# 2_mb_conn.net
KiCad netlist of a schematic drawn in Altium Designer
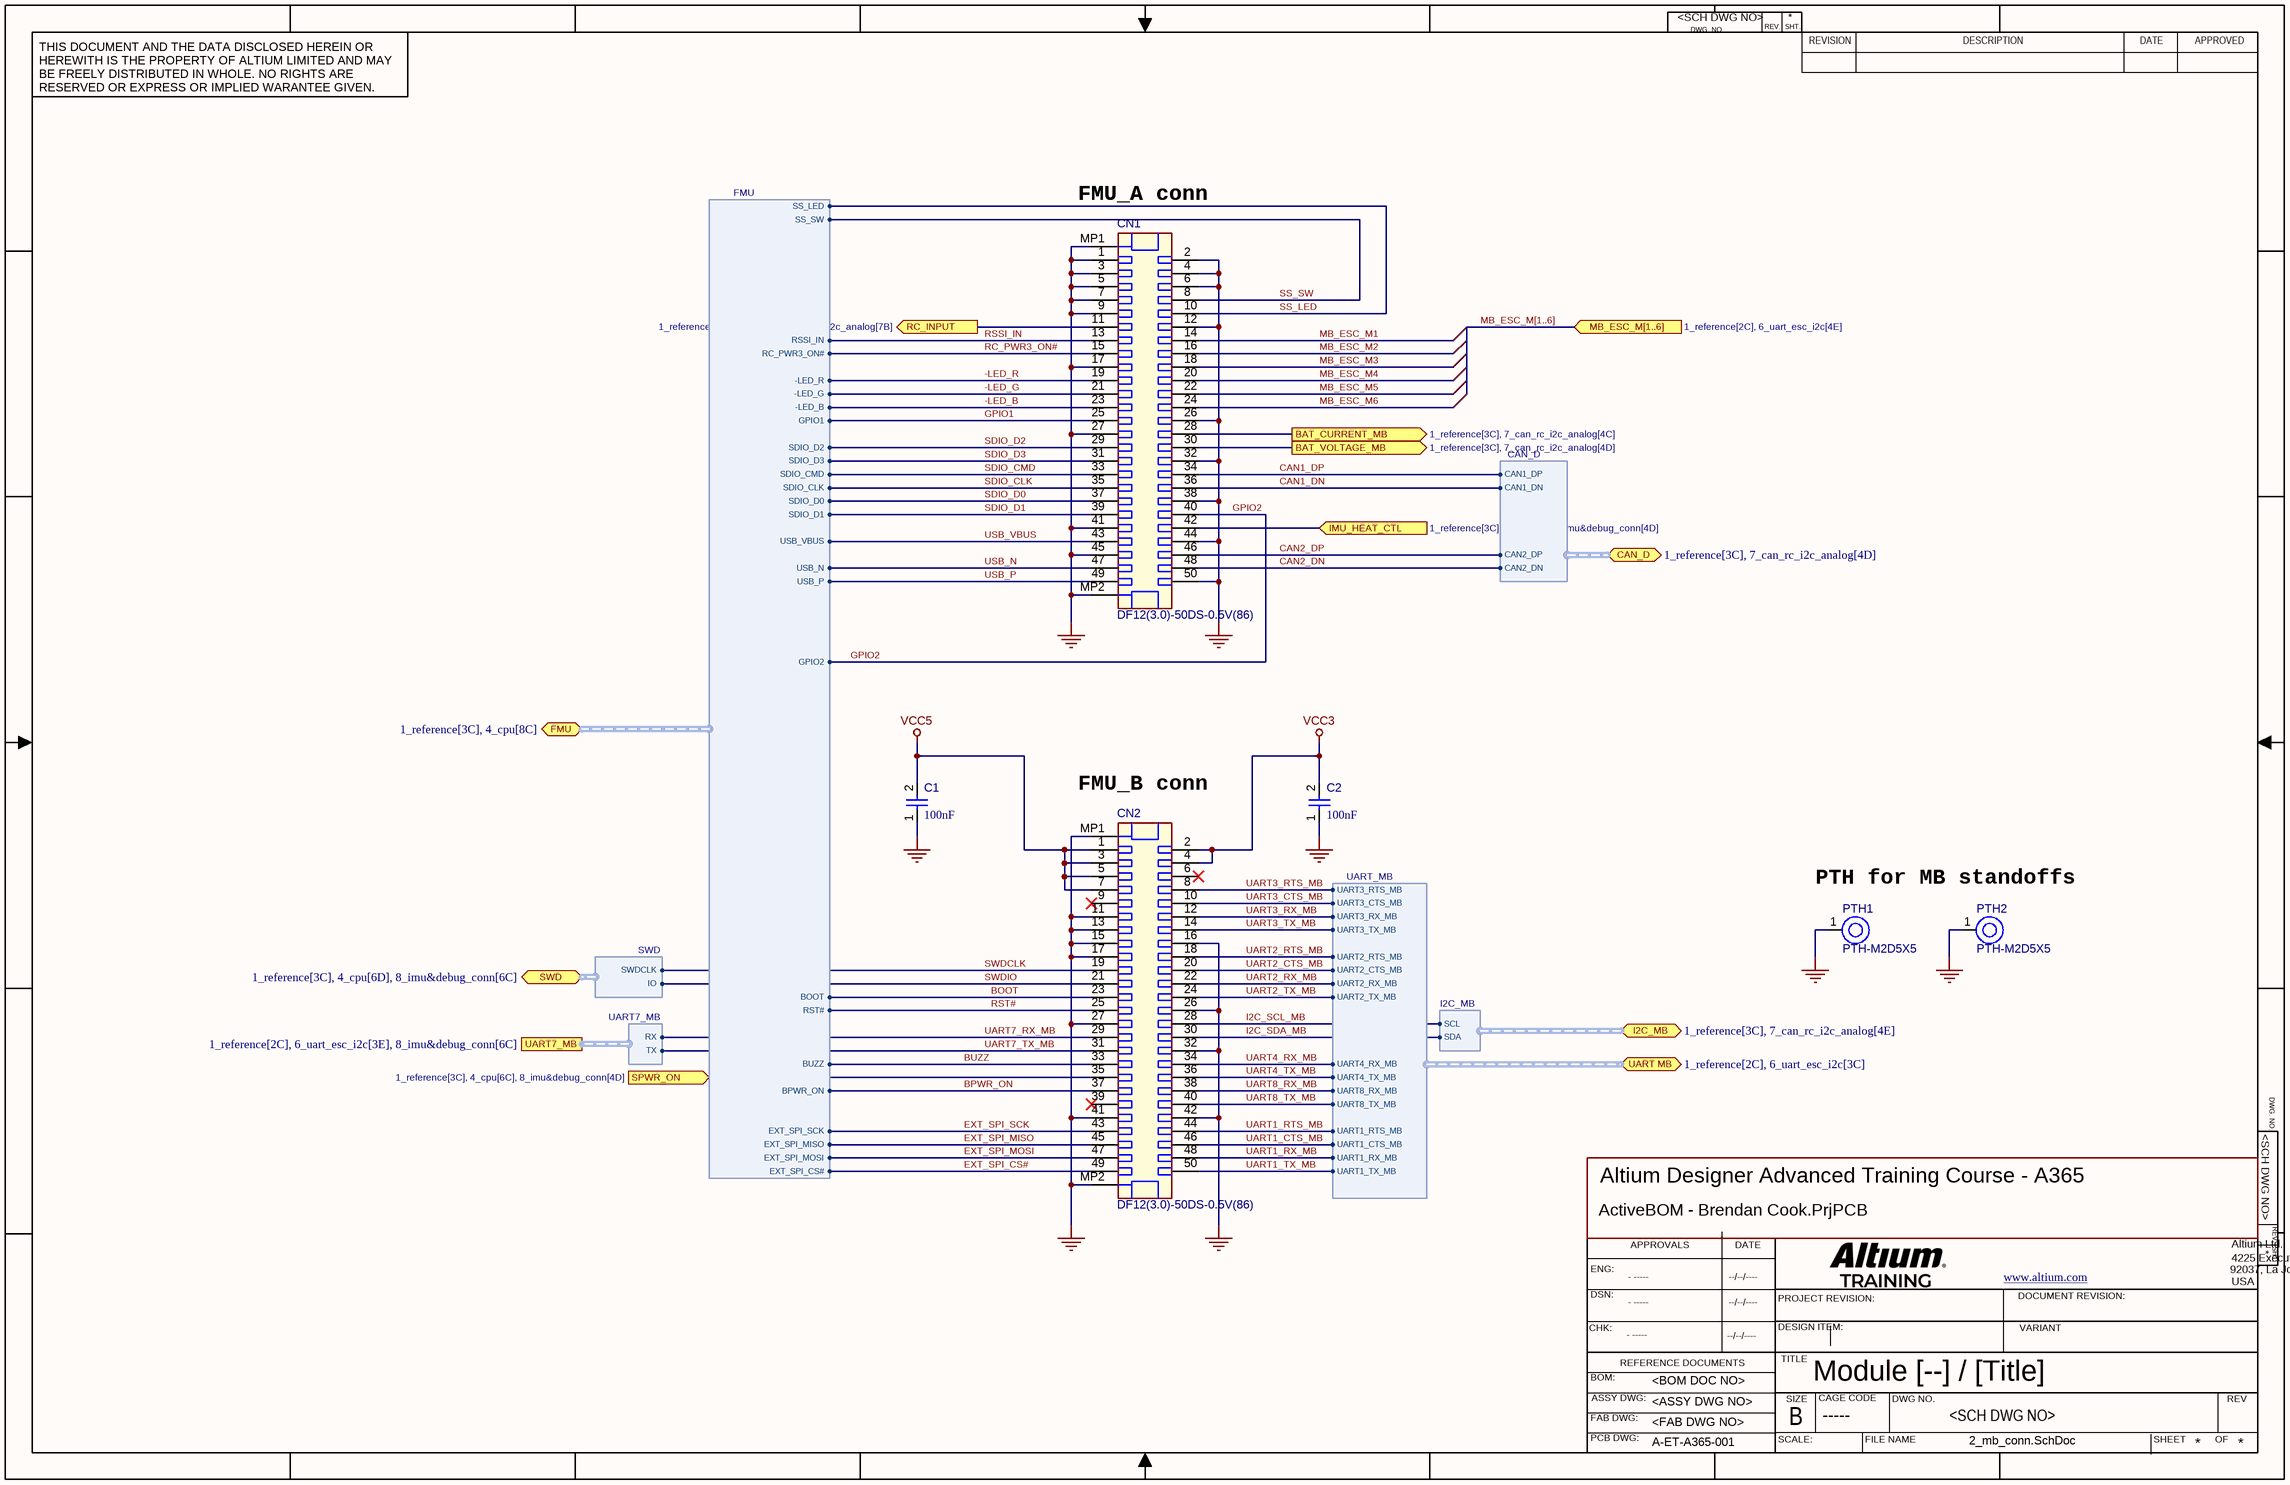
[diagram p0: 2_mb_conn.SchDoc]

(export (version "E")
  (design (tool "Eeschema 10.0.6"))
  (components
    (comp (ref "C1")
      (value "100nF")
      (footprint "CAPC0402(1005)60_L")
      (description "Chip Capacitor, 100nF +/-20%, 10V, 0402, Thickness 0.6 mm")
      (fields (field (name "TOLERANCE") "20%") (field (name "Comment") "Capacitor 100nF +/-20% 10V 0402"))
      (libsource (lib "MHH -  Altium Advanced Course A365 01") (part "CAP-NP-2"))
    )
    (comp (ref "C2")
      (value "100nF")
      (footprint "CAPC0402(1005)60_L")
      (description "Chip Capacitor, 100nF +/-20%, 10V, 0402, Thickness 0.6 mm")
      (fields (field (name "TOLERANCE") "20%") (field (name "Comment") "Capacitor 100nF +/-20% 10V 0402"))
      (libsource (lib "MHH -  Altium Advanced Course A365 01") (part "CAP-NP-2"))
    )
    (comp (ref "CN1")
      (value "DF12(3.0)-50DS-0.5V(86)")
      (footprint "HIRO-DF12(3.0)-50DS-0.5V_V")
      (description "Receptacle Connector, 50 V, 0.3 A, -45 to 125 degC, RoHS, Tape and Reel")
      (libsource (lib "MHH -  Altium Advanced Course A365 01") (part "CMP-00111-4"))
    )
    (comp (ref "CN2")
      (value "DF12(3.0)-50DS-0.5V(86)")
      (footprint "HIRO-DF12(3.0)-50DS-0.5V_V")
      (description "Receptacle Connector, 50 V, 0.3 A, -45 to 125 degC, RoHS, Tape and Reel")
      (libsource (lib "MHH -  Altium Advanced Course A365 01") (part "CMP-00111-4"))
    )
    (comp (ref "PTH1")
      (value "PTH-M2D5X5")
      (footprint "PTH-M2D5X5")
      (description "M2 PTH (2.5mm), 5mm pad")
      (libsource (lib "MHH -  Altium Advanced Course A365 01") (part "CMP-00028-00000-1"))
    )
    (comp (ref "PTH2")
      (value "PTH-M2D5X5")
      (footprint "PTH-M2D5X5")
      (description "M2 PTH (2.5mm), 5mm pad")
      (libsource (lib "MHH -  Altium Advanced Course A365 01") (part "CMP-00028-00000-1"))
    )
  )
  (nets
    (net (code "7") (name "/-LED_B") (class "Default")
      (node (ref "CN1") (pin "23") (pinfunction "23_23") (pintype "passive"))
    )
    (net (code "8") (name "/-LED_G") (class "Default")
      (node (ref "CN1") (pin "21") (pinfunction "21_21") (pintype "passive"))
    )
    (net (code "9") (name "/-LED_R") (class "Default")
      (node (ref "CN1") (pin "19") (pinfunction "19_19") (pintype "passive"))
    )
    (net (code "10") (name "/BAT_CURRENT_MB") (class "Default")
      (node (ref "CN1") (pin "28") (pinfunction "28_28") (pintype "passive"))
    )
    (net (code "11") (name "/BAT_VOLTAGE_MB") (class "Default")
      (node (ref "CN1") (pin "30") (pinfunction "30_30") (pintype "passive"))
    )
    (net (code "12") (name "/BOOT") (class "Default")
      (node (ref "CN2") (pin "23") (pinfunction "23_23") (pintype "passive"))
    )
    (net (code "13") (name "/BPWR_ON") (class "Default")
      (node (ref "CN2") (pin "37") (pinfunction "37_37") (pintype "passive"))
    )
    (net (code "14") (name "/BUZZ") (class "Default")
      (node (ref "CN2") (pin "33") (pinfunction "33_33") (pintype "passive"))
    )
    (net (code "15") (name "/CAN1_DN") (class "Default")
      (node (ref "CN1") (pin "36") (pinfunction "36_36") (pintype "passive"))
    )
    (net (code "16") (name "/CAN1_DP") (class "Default")
      (node (ref "CN1") (pin "34") (pinfunction "34_34") (pintype "passive"))
    )
    (net (code "17") (name "/CAN2_DN") (class "Default")
      (node (ref "CN1") (pin "48") (pinfunction "48_48") (pintype "passive"))
    )
    (net (code "18") (name "/CAN2_DP") (class "Default")
      (node (ref "CN1") (pin "46") (pinfunction "46_46") (pintype "passive"))
    )
    (net (code "19") (name "/EXT_SPI_CS#") (class "Default")
      (node (ref "CN2") (pin "49") (pinfunction "49_49") (pintype "passive"))
    )
    (net (code "20") (name "/EXT_SPI_MISO") (class "Default")
      (node (ref "CN2") (pin "45") (pinfunction "45_45") (pintype "passive"))
    )
    (net (code "21") (name "/EXT_SPI_MOSI") (class "Default")
      (node (ref "CN2") (pin "47") (pinfunction "47_47") (pintype "passive"))
    )
    (net (code "22") (name "/EXT_SPI_SCK") (class "Default")
      (node (ref "CN2") (pin "43") (pinfunction "43_43") (pintype "passive"))
    )
    (net (code "23") (name "/GPIO1") (class "Default")
      (node (ref "CN1") (pin "25") (pinfunction "25_25") (pintype "passive"))
    )
    (net (code "24") (name "/GPIO2") (class "Default")
      (node (ref "CN1") (pin "40") (pinfunction "40_40") (pintype "passive"))
    )
    (net (code "25") (name "/I2C_SCL_MB") (class "Default")
      (node (ref "CN2") (pin "28") (pinfunction "28_28") (pintype "passive"))
    )
    (net (code "26") (name "/I2C_SDA_MB") (class "Default")
      (node (ref "CN2") (pin "30") (pinfunction "30_30") (pintype "passive"))
    )
    (net (code "27") (name "/IMU_HEAT_CTL") (class "Default")
      (node (ref "CN1") (pin "42") (pinfunction "42_42") (pintype "passive"))
    )
    (net (code "28") (name "/MB_ESC_M1") (class "Default")
      (node (ref "CN1") (pin "14") (pinfunction "14_14") (pintype "passive"))
    )
    (net (code "29") (name "/MB_ESC_M2") (class "Default")
      (node (ref "CN1") (pin "16") (pinfunction "16_16") (pintype "passive"))
    )
    (net (code "30") (name "/MB_ESC_M3") (class "Default")
      (node (ref "CN1") (pin "18") (pinfunction "18_18") (pintype "passive"))
    )
    (net (code "31") (name "/MB_ESC_M4") (class "Default")
      (node (ref "CN1") (pin "20") (pinfunction "20_20") (pintype "passive"))
    )
    (net (code "32") (name "/MB_ESC_M5") (class "Default")
      (node (ref "CN1") (pin "22") (pinfunction "22_22") (pintype "passive"))
    )
    (net (code "33") (name "/MB_ESC_M6") (class "Default")
      (node (ref "CN1") (pin "24") (pinfunction "24_24") (pintype "passive"))
    )
    (net (code "35") (name "/RC_INPUT") (class "Default")
      (node (ref "CN1") (pin "11") (pinfunction "11_11") (pintype "passive"))
    )
    (net (code "36") (name "/RC_PWR3_ON#") (class "Default")
      (node (ref "CN1") (pin "15") (pinfunction "15_15") (pintype "passive"))
    )
    (net (code "37") (name "/RSSI_IN") (class "Default")
      (node (ref "CN1") (pin "13") (pinfunction "13_13") (pintype "passive"))
    )
    (net (code "38") (name "/RST#") (class "Default")
      (node (ref "CN2") (pin "25") (pinfunction "25_25") (pintype "passive"))
    )
    (net (code "39") (name "/SDIO_CLK") (class "Default")
      (node (ref "CN1") (pin "35") (pinfunction "35_35") (pintype "passive"))
    )
    (net (code "40") (name "/SDIO_CMD") (class "Default")
      (node (ref "CN1") (pin "33") (pinfunction "33_33") (pintype "passive"))
    )
    (net (code "41") (name "/SDIO_D0") (class "Default")
      (node (ref "CN1") (pin "37") (pinfunction "37_37") (pintype "passive"))
    )
    (net (code "42") (name "/SDIO_D1") (class "Default")
      (node (ref "CN1") (pin "39") (pinfunction "39_39") (pintype "passive"))
    )
    (net (code "43") (name "/SDIO_D2") (class "Default")
      (node (ref "CN1") (pin "29") (pinfunction "29_29") (pintype "passive"))
    )
    (net (code "44") (name "/SDIO_D3") (class "Default")
      (node (ref "CN1") (pin "31") (pinfunction "31_31") (pintype "passive"))
    )
    (net (code "45") (name "/SPWR_ON") (class "Default")
      (node (ref "CN2") (pin "35") (pinfunction "35_35") (pintype "passive"))
    )
    (net (code "46") (name "/SS_LED") (class "Default")
      (node (ref "CN1") (pin "10") (pinfunction "10_10") (pintype "passive"))
    )
    (net (code "47") (name "/SS_SW") (class "Default")
      (node (ref "CN1") (pin "8") (pinfunction "8_8") (pintype "passive"))
    )
    (net (code "48") (name "/SWDCLK") (class "Default")
      (node (ref "CN2") (pin "19") (pinfunction "19_19") (pintype "passive"))
    )
    (net (code "49") (name "/SWDIO") (class "Default")
      (node (ref "CN2") (pin "21") (pinfunction "21_21") (pintype "passive"))
    )
    (net (code "50") (name "/UART1_CTS_MB") (class "Default")
      (node (ref "CN2") (pin "46") (pinfunction "46_46") (pintype "passive"))
    )
    (net (code "51") (name "/UART1_RTS_MB") (class "Default")
      (node (ref "CN2") (pin "44") (pinfunction "44_44") (pintype "passive"))
    )
    (net (code "52") (name "/UART1_RX_MB") (class "Default")
      (node (ref "CN2") (pin "48") (pinfunction "48_48") (pintype "passive"))
    )
    (net (code "53") (name "/UART1_TX_MB") (class "Default")
      (node (ref "CN2") (pin "50") (pinfunction "50_50") (pintype "passive"))
    )
    (net (code "54") (name "/UART2_CTS_MB") (class "Default")
      (node (ref "CN2") (pin "20") (pinfunction "20_20") (pintype "passive"))
    )
    (net (code "55") (name "/UART2_RTS_MB") (class "Default")
      (node (ref "CN2") (pin "18") (pinfunction "18_18") (pintype "passive"))
    )
    (net (code "56") (name "/UART2_RX_MB") (class "Default")
      (node (ref "CN2") (pin "22") (pinfunction "22_22") (pintype "passive"))
    )
    (net (code "57") (name "/UART2_TX_MB") (class "Default")
      (node (ref "CN2") (pin "24") (pinfunction "24_24") (pintype "passive"))
    )
    (net (code "58") (name "/UART3_CTS_MB") (class "Default")
      (node (ref "CN2") (pin "10") (pinfunction "10_10") (pintype "passive"))
    )
    (net (code "59") (name "/UART3_RTS_MB") (class "Default")
      (node (ref "CN2") (pin "8") (pinfunction "8_8") (pintype "passive"))
    )
    (net (code "60") (name "/UART3_RX_MB") (class "Default")
      (node (ref "CN2") (pin "12") (pinfunction "12_12") (pintype "passive"))
    )
    (net (code "61") (name "/UART3_TX_MB") (class "Default")
      (node (ref "CN2") (pin "14") (pinfunction "14_14") (pintype "passive"))
    )
    (net (code "62") (name "/UART4_RX_MB") (class "Default")
      (node (ref "CN2") (pin "34") (pinfunction "34_34") (pintype "passive"))
    )
    (net (code "63") (name "/UART4_TX_MB") (class "Default")
      (node (ref "CN2") (pin "36") (pinfunction "36_36") (pintype "passive"))
    )
    (net (code "64") (name "/UART7_RX_MB") (class "Default")
      (node (ref "CN2") (pin "29") (pinfunction "29_29") (pintype "passive"))
    )
    (net (code "65") (name "/UART7_TX_MB") (class "Default")
      (node (ref "CN2") (pin "31") (pinfunction "31_31") (pintype "passive"))
    )
    (net (code "66") (name "/UART8_RX_MB") (class "Default")
      (node (ref "CN2") (pin "38") (pinfunction "38_38") (pintype "passive"))
    )
    (net (code "67") (name "/UART8_TX_MB") (class "Default")
      (node (ref "CN2") (pin "40") (pinfunction "40_40") (pintype "passive"))
    )
    (net (code "68") (name "/USB_N") (class "Default")
      (node (ref "CN1") (pin "47") (pinfunction "47_47") (pintype "passive"))
    )
    (net (code "69") (name "/USB_P") (class "Default")
      (node (ref "CN1") (pin "49") (pinfunction "49_49") (pintype "passive"))
    )
    (net (code "70") (name "/USB_VBUS") (class "Default")
      (node (ref "CN1") (pin "43") (pinfunction "43_43") (pintype "passive"))
    )
    (net (code "77") (name "GND") (class "Default")
      (node (ref "C1") (pin "1") (pinfunction "1_1") (pintype "passive"))
      (node (ref "C2") (pin "1") (pinfunction "1_1") (pintype "passive"))
      (node (ref "CN1") (pin "1") (pinfunction "1_1") (pintype "passive"))
      (node (ref "CN1") (pin "12") (pinfunction "12_12") (pintype "passive"))
      (node (ref "CN1") (pin "17") (pinfunction "17_17") (pintype "passive"))
      (node (ref "CN1") (pin "2") (pinfunction "2_2") (pintype "passive"))
      (node (ref "CN1") (pin "26") (pinfunction "26_26") (pintype "passive"))
      (node (ref "CN1") (pin "27") (pinfunction "27_27") (pintype "passive"))
      (node (ref "CN1") (pin "3") (pinfunction "3_3") (pintype "passive"))
      (node (ref "CN1") (pin "32") (pinfunction "32_32") (pintype "passive"))
      (node (ref "CN1") (pin "38") (pinfunction "38_38") (pintype "passive"))
      (node (ref "CN1") (pin "4") (pinfunction "4_4") (pintype "passive"))
      (node (ref "CN1") (pin "41") (pinfunction "41_41") (pintype "passive"))
      (node (ref "CN1") (pin "44") (pinfunction "44_44") (pintype "passive"))
      (node (ref "CN1") (pin "45") (pinfunction "45_45") (pintype "passive"))
      (node (ref "CN1") (pin "5") (pinfunction "5_5") (pintype "passive"))
      (node (ref "CN1") (pin "50") (pinfunction "50_50") (pintype "passive"))
      (node (ref "CN1") (pin "6") (pinfunction "6_6") (pintype "passive"))
      (node (ref "CN1") (pin "7") (pinfunction "7_7") (pintype "passive"))
      (node (ref "CN1") (pin "9") (pinfunction "9_9") (pintype "passive"))
      (node (ref "CN1") (pin "MP1") (pinfunction "MP1_MP1") (pintype "passive"))
      (node (ref "CN1") (pin "MP2") (pinfunction "MP2_MP2") (pintype "passive"))
      (node (ref "CN2") (pin "11") (pinfunction "11_11") (pintype "passive"))
      (node (ref "CN2") (pin "13") (pinfunction "13_13") (pintype "passive"))
      (node (ref "CN2") (pin "15") (pinfunction "15_15") (pintype "passive"))
      (node (ref "CN2") (pin "16") (pinfunction "16_16") (pintype "passive"))
      (node (ref "CN2") (pin "17") (pinfunction "17_17") (pintype "passive"))
      (node (ref "CN2") (pin "26") (pinfunction "26_26") (pintype "passive"))
      (node (ref "CN2") (pin "27") (pinfunction "27_27") (pintype "passive"))
      (node (ref "CN2") (pin "32") (pinfunction "32_32") (pintype "passive"))
      (node (ref "CN2") (pin "41") (pinfunction "41_41") (pintype "passive"))
      (node (ref "CN2") (pin "42") (pinfunction "42_42") (pintype "passive"))
      (node (ref "CN2") (pin "MP1") (pinfunction "MP1_MP1") (pintype "passive"))
      (node (ref "CN2") (pin "MP2") (pinfunction "MP2_MP2") (pintype "passive"))
      (node (ref "PTH1") (pin "1") (pinfunction "H1_1") (pintype "passive"))
      (node (ref "PTH2") (pin "1") (pinfunction "H1_1") (pintype "passive"))
    )
    (net (code "78") (name "VCC3") (class "Default")
      (node (ref "C2") (pin "2") (pinfunction "2_2") (pintype "passive"))
      (node (ref "CN2") (pin "2") (pinfunction "2_2") (pintype "passive"))
      (node (ref "CN2") (pin "4") (pinfunction "4_4") (pintype "passive"))
    )
    (net (code "79") (name "VCC5") (class "Default")
      (node (ref "C1") (pin "2") (pinfunction "2_2") (pintype "passive"))
      (node (ref "CN2") (pin "1") (pinfunction "1_1") (pintype "passive"))
      (node (ref "CN2") (pin "3") (pinfunction "3_3") (pintype "passive"))
      (node (ref "CN2") (pin "5") (pinfunction "5_5") (pintype "passive"))
      (node (ref "CN2") (pin "7") (pinfunction "7_7") (pintype "passive"))
    )
    (net (code "80") (name "unconnected-(CN2-Pad6)") (class "Default")
      (node (ref "CN2") (pin "6") (pinfunction "6_6") (pintype "passive+no_connect"))
    )
    (net (code "81") (name "unconnected-(CN2-Pad9)") (class "Default")
      (node (ref "CN2") (pin "9") (pinfunction "9_9") (pintype "passive+no_connect"))
    )
    (net (code "82") (name "unconnected-(CN2-Pad39)") (class "Default")
      (node (ref "CN2") (pin "39") (pinfunction "39_39") (pintype "passive+no_connect"))
    )
  )
)
